# Llethrau.net
KiCad netlist of a schematic drawn in EAGLE
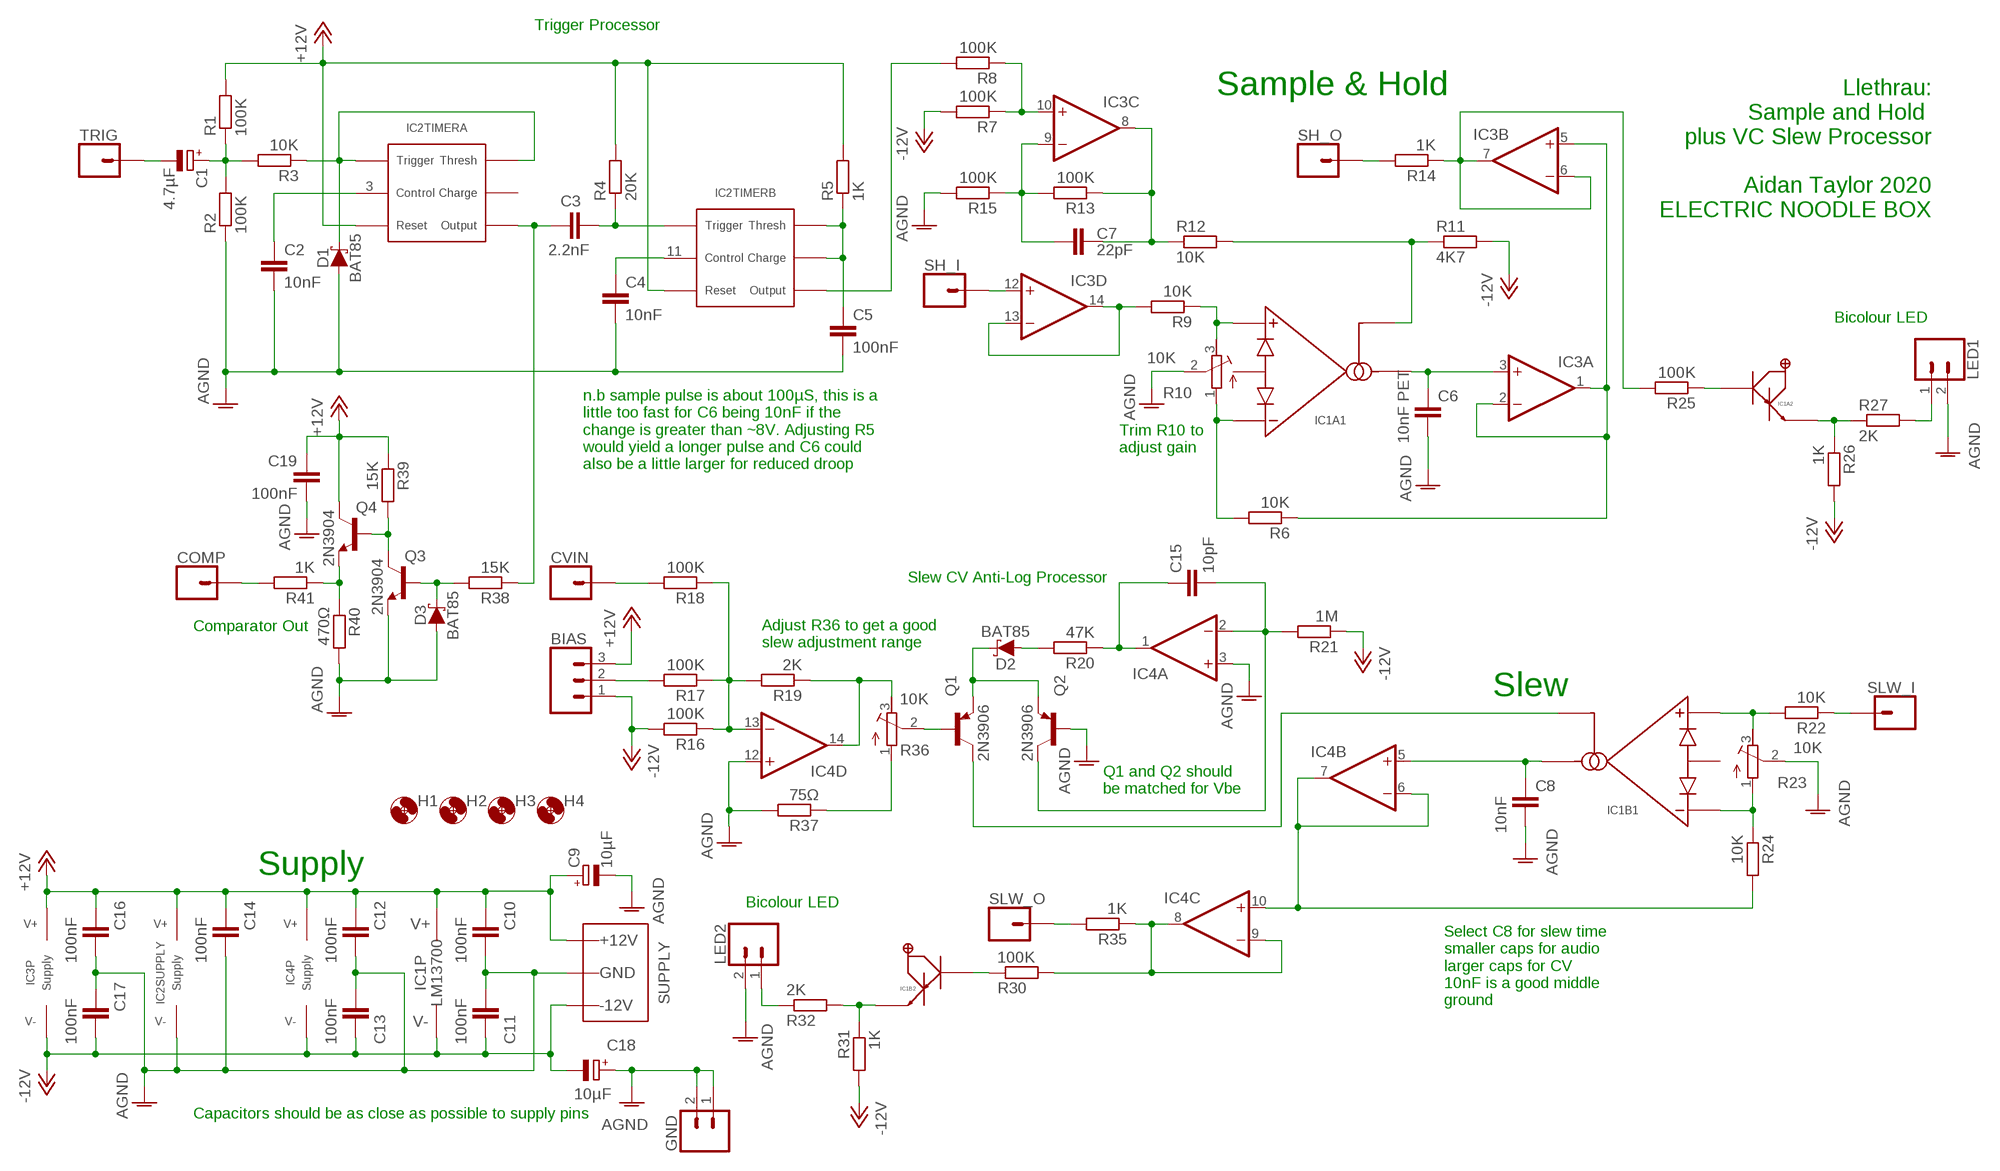
[diagram p0: schematic, sheet 1]

(export (version "E")
  (design (tool "Eeschema 10.0.6"))
  (components
    (comp (ref "BIAS")
      (value "3XWIREPAD")
      (footprint "eagle-import:1X03")
      (libsource (lib "eagle-import") (part "3XWIREPAD"))
    )
    (comp (ref "C1")
      (value "4.7µF")
      (footprint "eagle-import:E2,5-5")
      (libsource (lib "eagle-import") (part "CPOL-EUE2.5-5"))
    )
    (comp (ref "C2")
      (value "10nF")
      (footprint "eagle-import:C050-025X075")
      (libsource (lib "eagle-import") (part "C-EU050-025X075"))
    )
    (comp (ref "C3")
      (value "2.2nF")
      (footprint "eagle-import:C050-025X075")
      (libsource (lib "eagle-import") (part "C-EU050-025X075"))
    )
    (comp (ref "C4")
      (value "10nF")
      (footprint "eagle-import:C050-025X075")
      (libsource (lib "eagle-import") (part "C-EU050-025X075"))
    )
    (comp (ref "C5")
      (value "100nF")
      (footprint "eagle-import:C050-025X075")
      (libsource (lib "eagle-import") (part "C-EU050-025X075"))
    )
    (comp (ref "C6")
      (value "10nF PET")
      (footprint "eagle-import:C050-025X075")
      (libsource (lib "eagle-import") (part "C-EU050-025X075"))
    )
    (comp (ref "C7")
      (value "22pF")
      (footprint "eagle-import:C050-025X075")
      (libsource (lib "eagle-import") (part "C-EU050-025X075"))
    )
    (comp (ref "C8")
      (value "10nF")
      (footprint "eagle-import:C050-025X075")
      (libsource (lib "eagle-import") (part "C-EU050-025X075"))
    )
    (comp (ref "C9")
      (value "10µF")
      (footprint "eagle-import:E2,5-5")
      (libsource (lib "eagle-import") (part "CPOL-EUE2.5-5"))
    )
    (comp (ref "C10")
      (value "100nF")
      (footprint "eagle-import:C050-025X075")
      (libsource (lib "eagle-import") (part "C-EU050-025X075"))
    )
    (comp (ref "C11")
      (value "100nF")
      (footprint "eagle-import:C050-025X075")
      (libsource (lib "eagle-import") (part "C-EU050-025X075"))
    )
    (comp (ref "C12")
      (value "100nF")
      (footprint "eagle-import:C050-025X075")
      (libsource (lib "eagle-import") (part "C-EU050-025X075"))
    )
    (comp (ref "C13")
      (value "100nF")
      (footprint "eagle-import:C050-025X075")
      (libsource (lib "eagle-import") (part "C-EU050-025X075"))
    )
    (comp (ref "C14")
      (value "100nF")
      (footprint "eagle-import:C050-025X075")
      (libsource (lib "eagle-import") (part "C-EU050-025X075"))
    )
    (comp (ref "C15")
      (value "10pF")
      (footprint "eagle-import:C050-025X075")
      (libsource (lib "eagle-import") (part "C-EU050-025X075"))
    )
    (comp (ref "C16")
      (value "100nF")
      (footprint "eagle-import:C050-025X075")
      (libsource (lib "eagle-import") (part "C-EU050-025X075"))
    )
    (comp (ref "C17")
      (value "100nF")
      (footprint "eagle-import:C050-025X075")
      (libsource (lib "eagle-import") (part "C-EU050-025X075"))
    )
    (comp (ref "C18")
      (value "10µF")
      (footprint "eagle-import:E2,5-5")
      (libsource (lib "eagle-import") (part "CPOL-EUE2.5-5"))
    )
    (comp (ref "C19")
      (value "100nF")
      (footprint "eagle-import:C050-025X075")
      (libsource (lib "eagle-import") (part "C-EU050-025X075"))
    )
    (comp (ref "COMP")
      (value "1XWIREPAD")
      (footprint "eagle-import:1X01")
      (libsource (lib "eagle-import") (part "1XWIREPAD"))
    )
    (comp (ref "CVIN")
      (value "1XWIREPAD")
      (footprint "eagle-import:1X01")
      (libsource (lib "eagle-import") (part "1XWIREPAD"))
    )
    (comp (ref "D1")
      (value "BAT85")
      (footprint "eagle-import:DO35-7")
      (libsource (lib "eagle-import") (part "SCHOTTKY_DO35"))
    )
    (comp (ref "D2")
      (value "BAT85")
      (footprint "eagle-import:DO35-7")
      (libsource (lib "eagle-import") (part "SCHOTTKY_DO35"))
    )
    (comp (ref "D3")
      (value "BAT85")
      (footprint "eagle-import:DO35-7")
      (libsource (lib "eagle-import") (part "SCHOTTKY_DO35"))
    )
    (comp (ref "GND")
      (value "2XWIREPAD")
      (footprint "eagle-import:1X02")
      (libsource (lib "eagle-import") (part "2XWIREPAD"))
    )
    (comp (ref "H1")
      (value "MOUNT-HOLE3.2")
      (footprint "eagle-import:3,2")
      (libsource (lib "eagle-import") (part "MOUNT-HOLE3.2"))
    )
    (comp (ref "H2")
      (value "MOUNT-HOLE3.2")
      (footprint "eagle-import:3,2")
      (libsource (lib "eagle-import") (part "MOUNT-HOLE3.2"))
    )
    (comp (ref "H3")
      (value "MOUNT-HOLE3.2")
      (footprint "eagle-import:3,2")
      (libsource (lib "eagle-import") (part "MOUNT-HOLE3.2"))
    )
    (comp (ref "H4")
      (value "MOUNT-HOLE3.2")
      (footprint "eagle-import:3,2")
      (libsource (lib "eagle-import") (part "MOUNT-HOLE3.2"))
    )
    (comp (ref "IC1")
      (value "LM13700DIL")
      (footprint "eagle-import:DIL16")
      (libsource (lib "eagle-import") (part "LM13700DIL"))
    )
    (comp (ref "IC2")
      (value "556_DUALTIMERDIL14")
      (footprint "eagle-import:DIL14")
      (libsource (lib "eagle-import") (part "556_DUALTIMERDIL14"))
    )
    (comp (ref "IC3")
      (value "TL0X4DIL")
      (footprint "eagle-import:DIL14")
      (libsource (lib "eagle-import") (part "TL0X4DIL"))
    )
    (comp (ref "IC4")
      (value "TL0X4DIL")
      (footprint "eagle-import:DIL14")
      (libsource (lib "eagle-import") (part "TL0X4DIL"))
    )
    (comp (ref "LED1")
      (value "2XWIREPAD")
      (footprint "eagle-import:1X02")
      (libsource (lib "eagle-import") (part "2XWIREPAD"))
    )
    (comp (ref "LED2")
      (value "2XWIREPAD")
      (footprint "eagle-import:1X02")
      (libsource (lib "eagle-import") (part "2XWIREPAD"))
    )
    (comp (ref "Q1")
      (value "2N3906")
      (footprint "eagle-import:TO92")
      (libsource (lib "eagle-import") (part "2N3906"))
    )
    (comp (ref "Q2")
      (value "2N3906")
      (footprint "eagle-import:TO92")
      (libsource (lib "eagle-import") (part "2N3906"))
    )
    (comp (ref "Q3")
      (value "2N3904")
      (footprint "eagle-import:TO92")
      (libsource (lib "eagle-import") (part "2N3904"))
    )
    (comp (ref "Q4")
      (value "2N3904")
      (footprint "eagle-import:TO92")
      (libsource (lib "eagle-import") (part "2N3904"))
    )
    (comp (ref "R1")
      (value "100K")
      (footprint "eagle-import:0207_7")
      (libsource (lib "eagle-import") (part "R-EU_0207/7"))
    )
    (comp (ref "R2")
      (value "100K")
      (footprint "eagle-import:0207_7")
      (libsource (lib "eagle-import") (part "R-EU_0207/7"))
    )
    (comp (ref "R3")
      (value "10K")
      (footprint "eagle-import:0207_7")
      (libsource (lib "eagle-import") (part "R-EU_0207/7"))
    )
    (comp (ref "R4")
      (value "20K")
      (footprint "eagle-import:0207_7")
      (libsource (lib "eagle-import") (part "R-EU_0207/7"))
    )
    (comp (ref "R5")
      (value "1K")
      (footprint "eagle-import:0207_7")
      (libsource (lib "eagle-import") (part "R-EU_0207/7"))
    )
    (comp (ref "R6")
      (value "10K")
      (footprint "eagle-import:0207_7")
      (libsource (lib "eagle-import") (part "R-EU_0207/7"))
    )
    (comp (ref "R7")
      (value "100K")
      (footprint "eagle-import:0207_7")
      (libsource (lib "eagle-import") (part "R-EU_0207/7"))
    )
    (comp (ref "R8")
      (value "100K")
      (footprint "eagle-import:0207_7")
      (libsource (lib "eagle-import") (part "R-EU_0207/7"))
    )
    (comp (ref "R9")
      (value "10K")
      (footprint "eagle-import:0207_7")
      (libsource (lib "eagle-import") (part "R-EU_0207/7"))
    )
    (comp (ref "R10")
      (value "10K")
      (footprint "eagle-import:RTRIM3296W")
      (libsource (lib "eagle-import") (part "R-TRIMM3296W"))
    )
    (comp (ref "R11")
      (value "4K7")
      (footprint "eagle-import:0207_7")
      (libsource (lib "eagle-import") (part "R-EU_0207/7"))
    )
    (comp (ref "R12")
      (value "10K")
      (footprint "eagle-import:0207_7")
      (libsource (lib "eagle-import") (part "R-EU_0207/7"))
    )
    (comp (ref "R13")
      (value "100K")
      (footprint "eagle-import:0207_7")
      (libsource (lib "eagle-import") (part "R-EU_0207/7"))
    )
    (comp (ref "R14")
      (value "1K")
      (footprint "eagle-import:0207_7")
      (libsource (lib "eagle-import") (part "R-EU_0207/7"))
    )
    (comp (ref "R15")
      (value "100K")
      (footprint "eagle-import:0207_7")
      (libsource (lib "eagle-import") (part "R-EU_0207/7"))
    )
    (comp (ref "R16")
      (value "100K")
      (footprint "eagle-import:0207_7")
      (libsource (lib "eagle-import") (part "R-EU_0207/7"))
    )
    (comp (ref "R17")
      (value "100K")
      (footprint "eagle-import:0207_7")
      (libsource (lib "eagle-import") (part "R-EU_0207/7"))
    )
    (comp (ref "R18")
      (value "100K")
      (footprint "eagle-import:0207_7")
      (libsource (lib "eagle-import") (part "R-EU_0207/7"))
    )
    (comp (ref "R19")
      (value "2K")
      (footprint "eagle-import:0207_7")
      (libsource (lib "eagle-import") (part "R-EU_0207/7"))
    )
    (comp (ref "R20")
      (value "47K")
      (footprint "eagle-import:0207_7")
      (libsource (lib "eagle-import") (part "R-EU_0207/7"))
    )
    (comp (ref "R21")
      (value "1M")
      (footprint "eagle-import:0207_7")
      (libsource (lib "eagle-import") (part "R-EU_0207/7"))
    )
    (comp (ref "R22")
      (value "10K")
      (footprint "eagle-import:0207_7")
      (libsource (lib "eagle-import") (part "R-EU_0207/7"))
    )
    (comp (ref "R23")
      (value "10K")
      (footprint "eagle-import:RTRIM3296W")
      (libsource (lib "eagle-import") (part "R-TRIMM3296W"))
    )
    (comp (ref "R24")
      (value "10K")
      (footprint "eagle-import:0207_7")
      (libsource (lib "eagle-import") (part "R-EU_0207/7"))
    )
    (comp (ref "R25")
      (value "100K")
      (footprint "eagle-import:0207_7")
      (libsource (lib "eagle-import") (part "R-EU_0207/7"))
    )
    (comp (ref "R26")
      (value "1K")
      (footprint "eagle-import:0207_7")
      (libsource (lib "eagle-import") (part "R-EU_0207/7"))
    )
    (comp (ref "R27")
      (value "2K")
      (footprint "eagle-import:0207_7")
      (libsource (lib "eagle-import") (part "R-EU_0207/7"))
    )
    (comp (ref "R30")
      (value "100K")
      (footprint "eagle-import:0207_7")
      (libsource (lib "eagle-import") (part "R-EU_0207/7"))
    )
    (comp (ref "R31")
      (value "1K")
      (footprint "eagle-import:0207_7")
      (libsource (lib "eagle-import") (part "R-EU_0207/7"))
    )
    (comp (ref "R32")
      (value "2K")
      (footprint "eagle-import:0207_7")
      (libsource (lib "eagle-import") (part "R-EU_0207/7"))
    )
    (comp (ref "R35")
      (value "1K")
      (footprint "eagle-import:0207_7")
      (libsource (lib "eagle-import") (part "R-EU_0207/7"))
    )
    (comp (ref "R36")
      (value "10K")
      (footprint "eagle-import:RTRIM3296W")
      (libsource (lib "eagle-import") (part "R-TRIMM3296W"))
    )
    (comp (ref "R37")
      (value "75Ω")
      (footprint "eagle-import:0207_7")
      (libsource (lib "eagle-import") (part "R-EU_0207/7"))
    )
    (comp (ref "R38")
      (value "15K")
      (footprint "eagle-import:0207_7")
      (libsource (lib "eagle-import") (part "R-EU_0207/7"))
    )
    (comp (ref "R39")
      (value "15K")
      (footprint "eagle-import:0207_7")
      (libsource (lib "eagle-import") (part "R-EU_0207/7"))
    )
    (comp (ref "R40")
      (value "470Ω")
      (footprint "eagle-import:0207_7")
      (libsource (lib "eagle-import") (part "R-EU_0207/7"))
    )
    (comp (ref "R41")
      (value "1K")
      (footprint "eagle-import:0207_7")
      (libsource (lib "eagle-import") (part "R-EU_0207/7"))
    )
    (comp (ref "SH_I")
      (value "1XWIREPAD")
      (footprint "eagle-import:1X01")
      (libsource (lib "eagle-import") (part "1XWIREPAD"))
    )
    (comp (ref "SH_O")
      (value "1XWIREPAD")
      (footprint "eagle-import:1X01")
      (libsource (lib "eagle-import") (part "1XWIREPAD"))
    )
    (comp (ref "SLW_I")
      (value "1XWIREPAD")
      (footprint "eagle-import:1X01")
      (libsource (lib "eagle-import") (part "1XWIREPAD"))
    )
    (comp (ref "SLW_O")
      (value "1XWIREPAD")
      (footprint "eagle-import:1X01")
      (libsource (lib "eagle-import") (part "1XWIREPAD"))
    )
    (comp (ref "TRIG")
      (value "1XWIREPAD")
      (footprint "eagle-import:1X01")
      (libsource (lib "eagle-import") (part "1XWIREPAD"))
    )
    (comp (ref "WP1")
      (value "COMBO_SUPPLY_HEADER")
      (footprint "eagle-import:COMBINED_POWER")
      (libsource (lib "eagle-import") (part "COMBO_SUPPLY_HEADER"))
    )
  )
  (nets
    (net (code "1") (name "+12V") (class "Default")
      (node (ref "BIAS") (pin "3") (pinfunction "3_3") (pintype "passive"))
      (node (ref "C10") (pin "1") (pinfunction "1_1") (pintype "passive"))
      (node (ref "C12") (pin "1") (pinfunction "1_1") (pintype "passive"))
      (node (ref "C14") (pin "1") (pinfunction "1_1") (pintype "passive"))
      (node (ref "C16") (pin "1") (pinfunction "1_1") (pintype "passive"))
      (node (ref "C19") (pin "1") (pinfunction "1_1") (pintype "passive"))
      (node (ref "C9") (pin "+") (pinfunction "+_+") (pintype "passive"))
      (node (ref "IC1") (pin "11") (pinfunction "V+_11") (pintype "power_in"))
      (node (ref "IC2") (pin "10") (pinfunction "RESET_10") (pintype "bidirectional"))
      (node (ref "IC2") (pin "14") (pinfunction "V+_14") (pintype "bidirectional"))
      (node (ref "IC2") (pin "4") (pinfunction "RESET_4") (pintype "bidirectional"))
      (node (ref "IC3") (pin "4") (pinfunction "V+_4") (pintype "bidirectional"))
      (node (ref "IC4") (pin "4") (pinfunction "V+_4") (pintype "bidirectional"))
      (node (ref "Q4") (pin "1") (pinfunction "C_1") (pintype "passive"))
      (node (ref "R1") (pin "2") (pinfunction "2_2") (pintype "passive"))
      (node (ref "R39") (pin "1") (pinfunction "1_1") (pintype "passive"))
      (node (ref "R4") (pin "2") (pinfunction "2_2") (pintype "passive"))
      (node (ref "R5") (pin "2") (pinfunction "2_2") (pintype "passive"))
      (node (ref "WP1") (pin "V+1") (pinfunction "V++_V+1") (pintype "power_in"))
      (node (ref "WP1") (pin "V+2") (pinfunction "V++_V+2") (pintype "power_in"))
      (node (ref "WP1") (pin "V+3") (pinfunction "V++_V+3") (pintype "power_in"))
    )
    (net (code "2") (name "-12V") (class "Default")
      (node (ref "BIAS") (pin "1") (pinfunction "1_1") (pintype "passive"))
      (node (ref "C11") (pin "2") (pinfunction "2_2") (pintype "passive"))
      (node (ref "C13") (pin "2") (pinfunction "2_2") (pintype "passive"))
      (node (ref "C17") (pin "2") (pinfunction "2_2") (pintype "passive"))
      (node (ref "C18") (pin "-") (pinfunction "-_-") (pintype "passive"))
      (node (ref "IC1") (pin "6") (pinfunction "V-_6") (pintype "power_in"))
      (node (ref "IC3") (pin "11") (pinfunction "V-_11") (pintype "bidirectional"))
      (node (ref "IC4") (pin "11") (pinfunction "V-_11") (pintype "bidirectional"))
      (node (ref "R11") (pin "2") (pinfunction "2_2") (pintype "passive"))
      (node (ref "R16") (pin "2") (pinfunction "2_2") (pintype "passive"))
      (node (ref "R21") (pin "1") (pinfunction "1_1") (pintype "passive"))
      (node (ref "R26") (pin "2") (pinfunction "2_2") (pintype "passive"))
      (node (ref "R31") (pin "2") (pinfunction "2_2") (pintype "passive"))
      (node (ref "R7") (pin "2") (pinfunction "2_2") (pintype "passive"))
      (node (ref "WP1") (pin "V-1") (pinfunction "V--_V-1") (pintype "power_in"))
      (node (ref "WP1") (pin "V-2") (pinfunction "V--_V-2") (pintype "power_in"))
      (node (ref "WP1") (pin "V-3") (pinfunction "V--_V-3") (pintype "power_in"))
    )
    (net (code "3") (name "AGND") (class "Default")
      (node (ref "C10") (pin "2") (pinfunction "2_2") (pintype "passive"))
      (node (ref "C11") (pin "1") (pinfunction "1_1") (pintype "passive"))
      (node (ref "C12") (pin "2") (pinfunction "2_2") (pintype "passive"))
      (node (ref "C13") (pin "1") (pinfunction "1_1") (pintype "passive"))
      (node (ref "C14") (pin "2") (pinfunction "2_2") (pintype "passive"))
      (node (ref "C16") (pin "2") (pinfunction "2_2") (pintype "passive"))
      (node (ref "C17") (pin "1") (pinfunction "1_1") (pintype "passive"))
      (node (ref "C18") (pin "+") (pinfunction "+_+") (pintype "passive"))
      (node (ref "C19") (pin "2") (pinfunction "2_2") (pintype "passive"))
      (node (ref "C2") (pin "2") (pinfunction "2_2") (pintype "passive"))
      (node (ref "C4") (pin "2") (pinfunction "2_2") (pintype "passive"))
      (node (ref "C5") (pin "2") (pinfunction "2_2") (pintype "passive"))
      (node (ref "C6") (pin "2") (pinfunction "2_2") (pintype "passive"))
      (node (ref "C8") (pin "2") (pinfunction "2_2") (pintype "passive"))
      (node (ref "C9") (pin "-") (pinfunction "-_-") (pintype "passive"))
      (node (ref "D1") (pin "A") (pinfunction "A_A") (pintype "passive"))
      (node (ref "D3") (pin "A") (pinfunction "A_A") (pintype "passive"))
      (node (ref "GND") (pin "1") (pinfunction "1_1") (pintype "passive"))
      (node (ref "GND") (pin "2") (pinfunction "2_2") (pintype "passive"))
      (node (ref "IC2") (pin "7") (pinfunction "V-_7") (pintype "bidirectional"))
      (node (ref "IC4") (pin "12") (pinfunction "+IN_12") (pintype "input"))
      (node (ref "IC4") (pin "3") (pinfunction "+IN_3") (pintype "input"))
      (node (ref "LED1") (pin "2") (pinfunction "2_2") (pintype "passive"))
      (node (ref "LED2") (pin "2") (pinfunction "2_2") (pintype "passive"))
      (node (ref "Q2") (pin "2") (pinfunction "B_2") (pintype "passive"))
      (node (ref "Q3") (pin "3") (pinfunction "E_3") (pintype "passive"))
      (node (ref "R10") (pin "2") (pinfunction "S_2") (pintype "passive"))
      (node (ref "R15") (pin "2") (pinfunction "2_2") (pintype "passive"))
      (node (ref "R2") (pin "1") (pinfunction "1_1") (pintype "passive"))
      (node (ref "R23") (pin "2") (pinfunction "S_2") (pintype "passive"))
      (node (ref "R37") (pin "2") (pinfunction "2_2") (pintype "passive"))
      (node (ref "R40") (pin "2") (pinfunction "2_2") (pintype "passive"))
      (node (ref "WP1") (pin "GND1") (pinfunction "AGND_GND1") (pintype "power_in"))
      (node (ref "WP1") (pin "GND2") (pinfunction "AGND_GND2") (pintype "power_in"))
      (node (ref "WP1") (pin "GND3") (pinfunction "AGND_GND3") (pintype "power_in"))
      (node (ref "WP1") (pin "GND4") (pinfunction "AGND_GND4") (pintype "power_in"))
      (node (ref "WP1") (pin "GND5") (pinfunction "AGND_GND5") (pintype "power_in"))
      (node (ref "WP1") (pin "GND6") (pinfunction "AGND_GND6") (pintype "power_in"))
      (node (ref "WP1") (pin "GND7") (pinfunction "AGND_GND7") (pintype "power_in"))
      (node (ref "WP1") (pin "GND8") (pinfunction "AGND_GND8") (pintype "power_in"))
    )
    (net (code "4") (name "Net-(BIAS-Pad2)") (class "Default")
      (node (ref "BIAS") (pin "2") (pinfunction "2_2") (pintype "passive"))
      (node (ref "R17") (pin "2") (pinfunction "2_2") (pintype "passive"))
    )
    (net (code "5") (name "Net-(C1-Pad+)") (class "Default")
      (node (ref "C1") (pin "+") (pinfunction "+_+") (pintype "passive"))
      (node (ref "R1") (pin "1") (pinfunction "1_1") (pintype "passive"))
      (node (ref "R2") (pin "2") (pinfunction "2_2") (pintype "passive"))
      (node (ref "R3") (pin "2") (pinfunction "2_2") (pintype "passive"))
    )
    (net (code "6") (name "Net-(C1-Pad-)") (class "Default")
      (node (ref "C1") (pin "-") (pinfunction "-_-") (pintype "passive"))
      (node (ref "TRIG") (pin "1") (pinfunction "1_1") (pintype "passive"))
    )
    (net (code "7") (name "Net-(COMP-Pad1)") (class "Default")
      (node (ref "COMP") (pin "1") (pinfunction "1_1") (pintype "passive"))
      (node (ref "R41") (pin "2") (pinfunction "2_2") (pintype "passive"))
    )
    (net (code "8") (name "Net-(CVIN-Pad1)") (class "Default")
      (node (ref "CVIN") (pin "1") (pinfunction "1_1") (pintype "passive"))
      (node (ref "R18") (pin "2") (pinfunction "2_2") (pintype "passive"))
    )
    (net (code "9") (name "Net-(D2-PadA)") (class "Default")
      (node (ref "D2") (pin "A") (pinfunction "A_A") (pintype "passive"))
      (node (ref "R20") (pin "2") (pinfunction "2_2") (pintype "passive"))
    )
    (net (code "10") (name "Net-(IC1A-AMP+)") (class "Default")
      (node (ref "IC1") (pin "3") (pinfunction "AMP+_3") (pintype "input"))
      (node (ref "R10") (pin "3") (pinfunction "E_3") (pintype "passive"))
      (node (ref "R9") (pin "1") (pinfunction "1_1") (pintype "passive"))
    )
    (net (code "11") (name "Net-(IC1A-AMP-)") (class "Default")
      (node (ref "IC1") (pin "4") (pinfunction "AMP-_4") (pintype "input"))
      (node (ref "R10") (pin "1") (pinfunction "A_1") (pintype "passive"))
      (node (ref "R6") (pin "2") (pinfunction "2_2") (pintype "passive"))
    )
    (net (code "12") (name "Net-(IC1A-AMPBIAS)") (class "Default")
      (node (ref "IC1") (pin "1") (pinfunction "AMPBIAS_1") (pintype "input"))
      (node (ref "R11") (pin "1") (pinfunction "1_1") (pintype "passive"))
      (node (ref "R12") (pin "2") (pinfunction "2_2") (pintype "passive"))
    )
    (net (code "13") (name "Net-(IC1A-AMPOUT)") (class "Default")
      (node (ref "C6") (pin "1") (pinfunction "1_1") (pintype "passive"))
      (node (ref "IC1") (pin "5") (pinfunction "AMPOUT_5") (pintype "output"))
      (node (ref "IC3") (pin "3") (pinfunction "+IN_3") (pintype "input"))
    )
    (net (code "14") (name "Net-(IC1B-BUFF_IN)") (class "Default")
      (node (ref "IC1") (pin "7") (pinfunction "BUFF_IN_7") (pintype "input"))
      (node (ref "R25") (pin "1") (pinfunction "1_1") (pintype "passive"))
    )
    (net (code "15") (name "Net-(IC1B-BUFF_OUT)") (class "Default")
      (node (ref "IC1") (pin "8") (pinfunction "BUFF_OUT_8") (pintype "bidirectional"))
      (node (ref "R26") (pin "1") (pinfunction "1_1") (pintype "passive"))
      (node (ref "R27") (pin "1") (pinfunction "1_1") (pintype "passive"))
    )
    (net (code "16") (name "Net-(IC1C-AMP+)") (class "Default")
      (node (ref "IC1") (pin "14") (pinfunction "AMP+_14") (pintype "input"))
      (node (ref "R22") (pin "2") (pinfunction "2_2") (pintype "passive"))
      (node (ref "R23") (pin "3") (pinfunction "E_3") (pintype "passive"))
    )
    (net (code "17") (name "Net-(IC1C-AMP-)") (class "Default")
      (node (ref "IC1") (pin "13") (pinfunction "AMP-_13") (pintype "input"))
      (node (ref "R23") (pin "1") (pinfunction "A_1") (pintype "passive"))
      (node (ref "R24") (pin "1") (pinfunction "1_1") (pintype "passive"))
    )
    (net (code "18") (name "Net-(IC1C-AMPBIAS)") (class "Default")
      (node (ref "IC1") (pin "16") (pinfunction "AMPBIAS_16") (pintype "input"))
      (node (ref "Q1") (pin "1") (pinfunction "C_1") (pintype "passive"))
    )
    (net (code "19") (name "Net-(IC1C-AMPOUT)") (class "Default")
      (node (ref "C8") (pin "1") (pinfunction "1_1") (pintype "passive"))
      (node (ref "IC1") (pin "12") (pinfunction "AMPOUT_12") (pintype "output"))
      (node (ref "IC4") (pin "5") (pinfunction "+IN_5") (pintype "input"))
    )
    (net (code "20") (name "Net-(IC1D-BUFF_IN)") (class "Default")
      (node (ref "IC1") (pin "10") (pinfunction "BUFF_IN_10") (pintype "input"))
      (node (ref "R30") (pin "1") (pinfunction "1_1") (pintype "passive"))
    )
    (net (code "21") (name "Net-(IC1D-BUFF_OUT)") (class "Default")
      (node (ref "IC1") (pin "9") (pinfunction "BUFF_OUT_9") (pintype "bidirectional"))
      (node (ref "R31") (pin "1") (pinfunction "1_1") (pintype "passive"))
      (node (ref "R32") (pin "2") (pinfunction "2_2") (pintype "passive"))
    )
    (net (code "22") (name "Net-(IC2B-CONT)") (class "Default")
      (node (ref "C2") (pin "1") (pinfunction "1_1") (pintype "passive"))
      (node (ref "IC2") (pin "3") (pinfunction "CONT_3") (pintype "bidirectional"))
    )
    (net (code "23") (name "Net-(IC2B-OUTPUT)") (class "Default")
      (node (ref "C3") (pin "1") (pinfunction "1_1") (pintype "passive"))
      (node (ref "IC2") (pin "5") (pinfunction "OUTPUT_5") (pintype "bidirectional"))
      (node (ref "R38") (pin "1") (pinfunction "1_1") (pintype "passive"))
    )
    (net (code "24") (name "Net-(IC2B-THRESHOLD)") (class "Default")
      (node (ref "D1") (pin "C") (pinfunction "C_C") (pintype "passive"))
      (node (ref "IC2") (pin "2") (pinfunction "THRESHOLD_2") (pintype "bidirectional"))
      (node (ref "IC2") (pin "6") (pinfunction "TRIGGER_6") (pintype "bidirectional"))
      (node (ref "R3") (pin "1") (pinfunction "1_1") (pintype "passive"))
    )
    (net (code "25") (name "Net-(IC2C-CONT)") (class "Default")
      (node (ref "C4") (pin "1") (pinfunction "1_1") (pintype "passive"))
      (node (ref "IC2") (pin "11") (pinfunction "CONT_11") (pintype "bidirectional"))
    )
    (net (code "26") (name "Net-(IC2C-DISCHARGE)") (class "Default")
      (node (ref "C5") (pin "1") (pinfunction "1_1") (pintype "passive"))
      (node (ref "IC2") (pin "12") (pinfunction "THRESHOLD_12") (pintype "bidirectional"))
      (node (ref "IC2") (pin "13") (pinfunction "DISCHARGE_13") (pintype "bidirectional"))
      (node (ref "R5") (pin "1") (pinfunction "1_1") (pintype "passive"))
    )
    (net (code "27") (name "Net-(IC2C-OUTPUT)") (class "Default")
      (node (ref "IC2") (pin "9") (pinfunction "OUTPUT_9") (pintype "bidirectional"))
      (node (ref "R8") (pin "2") (pinfunction "2_2") (pintype "passive"))
    )
    (net (code "28") (name "Net-(IC2C-TRIGGER)") (class "Default")
      (node (ref "C3") (pin "2") (pinfunction "2_2") (pintype "passive"))
      (node (ref "IC2") (pin "8") (pinfunction "TRIGGER_8") (pintype "bidirectional"))
      (node (ref "R4") (pin "1") (pinfunction "1_1") (pintype "passive"))
    )
    (net (code "29") (name "Net-(IC3A--IN)") (class "Default")
      (node (ref "IC3") (pin "1") (pinfunction "OUT_1") (pintype "output"))
      (node (ref "IC3") (pin "2") (pinfunction "-IN_2") (pintype "input"))
      (node (ref "IC3") (pin "5") (pinfunction "+IN_5") (pintype "input"))
      (node (ref "R6") (pin "1") (pinfunction "1_1") (pintype "passive"))
    )
    (net (code "30") (name "Net-(IC3B--IN)") (class "Default")
      (node (ref "IC3") (pin "6") (pinfunction "-IN_6") (pintype "input"))
      (node (ref "IC3") (pin "7") (pinfunction "OUT_7") (pintype "output"))
      (node (ref "R14") (pin "1") (pinfunction "1_1") (pintype "passive"))
      (node (ref "R25") (pin "2") (pinfunction "2_2") (pintype "passive"))
    )
    (net (code "31") (name "Net-(IC3C-+IN)") (class "Default")
      (node (ref "IC3") (pin "10") (pinfunction "+IN_10") (pintype "input"))
      (node (ref "R7") (pin "1") (pinfunction "1_1") (pintype "passive"))
      (node (ref "R8") (pin "1") (pinfunction "1_1") (pintype "passive"))
    )
    (net (code "32") (name "Net-(IC3C--IN)") (class "Default")
      (node (ref "C7") (pin "1") (pinfunction "1_1") (pintype "passive"))
      (node (ref "IC3") (pin "9") (pinfunction "-IN_9") (pintype "input"))
      (node (ref "R13") (pin "2") (pinfunction "2_2") (pintype "passive"))
      (node (ref "R15") (pin "1") (pinfunction "1_1") (pintype "passive"))
    )
    (net (code "33") (name "Net-(IC3C-OUT)") (class "Default")
      (node (ref "C7") (pin "2") (pinfunction "2_2") (pintype "passive"))
      (node (ref "IC3") (pin "8") (pinfunction "OUT_8") (pintype "output"))
      (node (ref "R12") (pin "1") (pinfunction "1_1") (pintype "passive"))
      (node (ref "R13") (pin "1") (pinfunction "1_1") (pintype "passive"))
    )
    (net (code "34") (name "Net-(IC3D-+IN)") (class "Default")
      (node (ref "IC3") (pin "12") (pinfunction "+IN_12") (pintype "input"))
      (node (ref "SH_I") (pin "1") (pinfunction "1_1") (pintype "passive"))
    )
    (net (code "35") (name "Net-(IC3D--IN)") (class "Default")
      (node (ref "IC3") (pin "13") (pinfunction "-IN_13") (pintype "input"))
      (node (ref "IC3") (pin "14") (pinfunction "OUT_14") (pintype "output"))
      (node (ref "R9") (pin "2") (pinfunction "2_2") (pintype "passive"))
    )
    (net (code "36") (name "Net-(IC4A--IN)") (class "Default")
      (node (ref "C15") (pin "2") (pinfunction "2_2") (pintype "passive"))
      (node (ref "IC4") (pin "2") (pinfunction "-IN_2") (pintype "input"))
      (node (ref "Q2") (pin "1") (pinfunction "C_1") (pintype "passive"))
      (node (ref "R21") (pin "2") (pinfunction "2_2") (pintype "passive"))
    )
    (net (code "37") (name "Net-(IC4A-OUT)") (class "Default")
      (node (ref "C15") (pin "1") (pinfunction "1_1") (pintype "passive"))
      (node (ref "IC4") (pin "1") (pinfunction "OUT_1") (pintype "output"))
      (node (ref "R20") (pin "1") (pinfunction "1_1") (pintype "passive"))
    )
    (net (code "38") (name "Net-(IC4B--IN)") (class "Default")
      (node (ref "IC4") (pin "10") (pinfunction "+IN_10") (pintype "input"))
      (node (ref "IC4") (pin "6") (pinfunction "-IN_6") (pintype "input"))
      (node (ref "IC4") (pin "7") (pinfunction "OUT_7") (pintype "output"))
      (node (ref "R24") (pin "2") (pinfunction "2_2") (pintype "passive"))
    )
    (net (code "39") (name "Net-(IC4C--IN)") (class "Default")
      (node (ref "IC4") (pin "8") (pinfunction "OUT_8") (pintype "output"))
      (node (ref "IC4") (pin "9") (pinfunction "-IN_9") (pintype "input"))
      (node (ref "R30") (pin "2") (pinfunction "2_2") (pintype "passive"))
      (node (ref "R35") (pin "1") (pinfunction "1_1") (pintype "passive"))
    )
    (net (code "40") (name "Net-(IC4D--IN)") (class "Default")
      (node (ref "IC4") (pin "13") (pinfunction "-IN_13") (pintype "input"))
      (node (ref "R16") (pin "1") (pinfunction "1_1") (pintype "passive"))
      (node (ref "R17") (pin "1") (pinfunction "1_1") (pintype "passive"))
      (node (ref "R18") (pin "1") (pinfunction "1_1") (pintype "passive"))
      (node (ref "R19") (pin "2") (pinfunction "2_2") (pintype "passive"))
    )
    (net (code "41") (name "Net-(IC4D-OUT)") (class "Default")
      (node (ref "IC4") (pin "14") (pinfunction "OUT_14") (pintype "output"))
      (node (ref "R19") (pin "1") (pinfunction "1_1") (pintype "passive"))
      (node (ref "R36") (pin "3") (pinfunction "E_3") (pintype "passive"))
    )
    (net (code "42") (name "Net-(LED1-Pad1)") (class "Default")
      (node (ref "LED1") (pin "1") (pinfunction "1_1") (pintype "passive"))
      (node (ref "R27") (pin "2") (pinfunction "2_2") (pintype "passive"))
    )
    (net (code "43") (name "Net-(LED2-Pad1)") (class "Default")
      (node (ref "LED2") (pin "1") (pinfunction "1_1") (pintype "passive"))
      (node (ref "R32") (pin "1") (pinfunction "1_1") (pintype "passive"))
    )
    (net (code "44") (name "Net-(Q1-B)") (class "Default")
      (node (ref "Q1") (pin "2") (pinfunction "B_2") (pintype "passive"))
      (node (ref "R36") (pin "2") (pinfunction "S_2") (pintype "passive"))
    )
    (net (code "45") (name "Net-(Q1-E)") (class "Default")
      (node (ref "D2") (pin "C") (pinfunction "C_C") (pintype "passive"))
      (node (ref "Q1") (pin "3") (pinfunction "E_3") (pintype "passive"))
      (node (ref "Q2") (pin "3") (pinfunction "E_3") (pintype "passive"))
    )
    (net (code "46") (name "Net-(Q3-B)") (class "Default")
      (node (ref "D3") (pin "C") (pinfunction "C_C") (pintype "passive"))
      (node (ref "Q3") (pin "2") (pinfunction "B_2") (pintype "passive"))
      (node (ref "R38") (pin "2") (pinfunction "2_2") (pintype "passive"))
    )
    (net (code "47") (name "Net-(Q3-C)") (class "Default")
      (node (ref "Q3") (pin "1") (pinfunction "C_1") (pintype "passive"))
      (node (ref "Q4") (pin "2") (pinfunction "B_2") (pintype "passive"))
      (node (ref "R39") (pin "2") (pinfunction "2_2") (pintype "passive"))
    )
    (net (code "48") (name "Net-(Q4-E)") (class "Default")
      (node (ref "Q4") (pin "3") (pinfunction "E_3") (pintype "passive"))
      (node (ref "R40") (pin "1") (pinfunction "1_1") (pintype "passive"))
      (node (ref "R41") (pin "1") (pinfunction "1_1") (pintype "passive"))
    )
    (net (code "49") (name "Net-(R14-Pad2)") (class "Default")
      (node (ref "R14") (pin "2") (pinfunction "2_2") (pintype "passive"))
      (node (ref "SH_O") (pin "1") (pinfunction "1_1") (pintype "passive"))
    )
    (net (code "50") (name "Net-(R22-Pad1)") (class "Default")
      (node (ref "R22") (pin "1") (pinfunction "1_1") (pintype "passive"))
      (node (ref "SLW_I") (pin "1") (pinfunction "1_1") (pintype "passive"))
    )
    (net (code "51") (name "Net-(R35-Pad2)") (class "Default")
      (node (ref "R35") (pin "2") (pinfunction "2_2") (pintype "passive"))
      (node (ref "SLW_O") (pin "1") (pinfunction "1_1") (pintype "passive"))
    )
    (net (code "52") (name "Net-(R36-A)") (class "Default")
      (node (ref "R36") (pin "1") (pinfunction "A_1") (pintype "passive"))
      (node (ref "R37") (pin "1") (pinfunction "1_1") (pintype "passive"))
    )
    (net (code "53") (name "unconnected-(IC1A-DIODES-Pad2)") (class "Default")
      (node (ref "IC1") (pin "2") (pinfunction "DIODES_2") (pintype "input"))
    )
    (net (code "54") (name "unconnected-(IC1C-DIODES-Pad15)") (class "Default")
      (node (ref "IC1") (pin "15") (pinfunction "DIODES_15") (pintype "input"))
    )
    (net (code "55") (name "unconnected-(IC2B-DISCHARGE-Pad1)") (class "Default")
      (node (ref "IC2") (pin "1") (pinfunction "DISCHARGE_1") (pintype "bidirectional"))
    )
  )
)
